# SCH_WROBD_2022_2022-09-23.net
KiCad netlist of a schematic drawn in EasyEDA
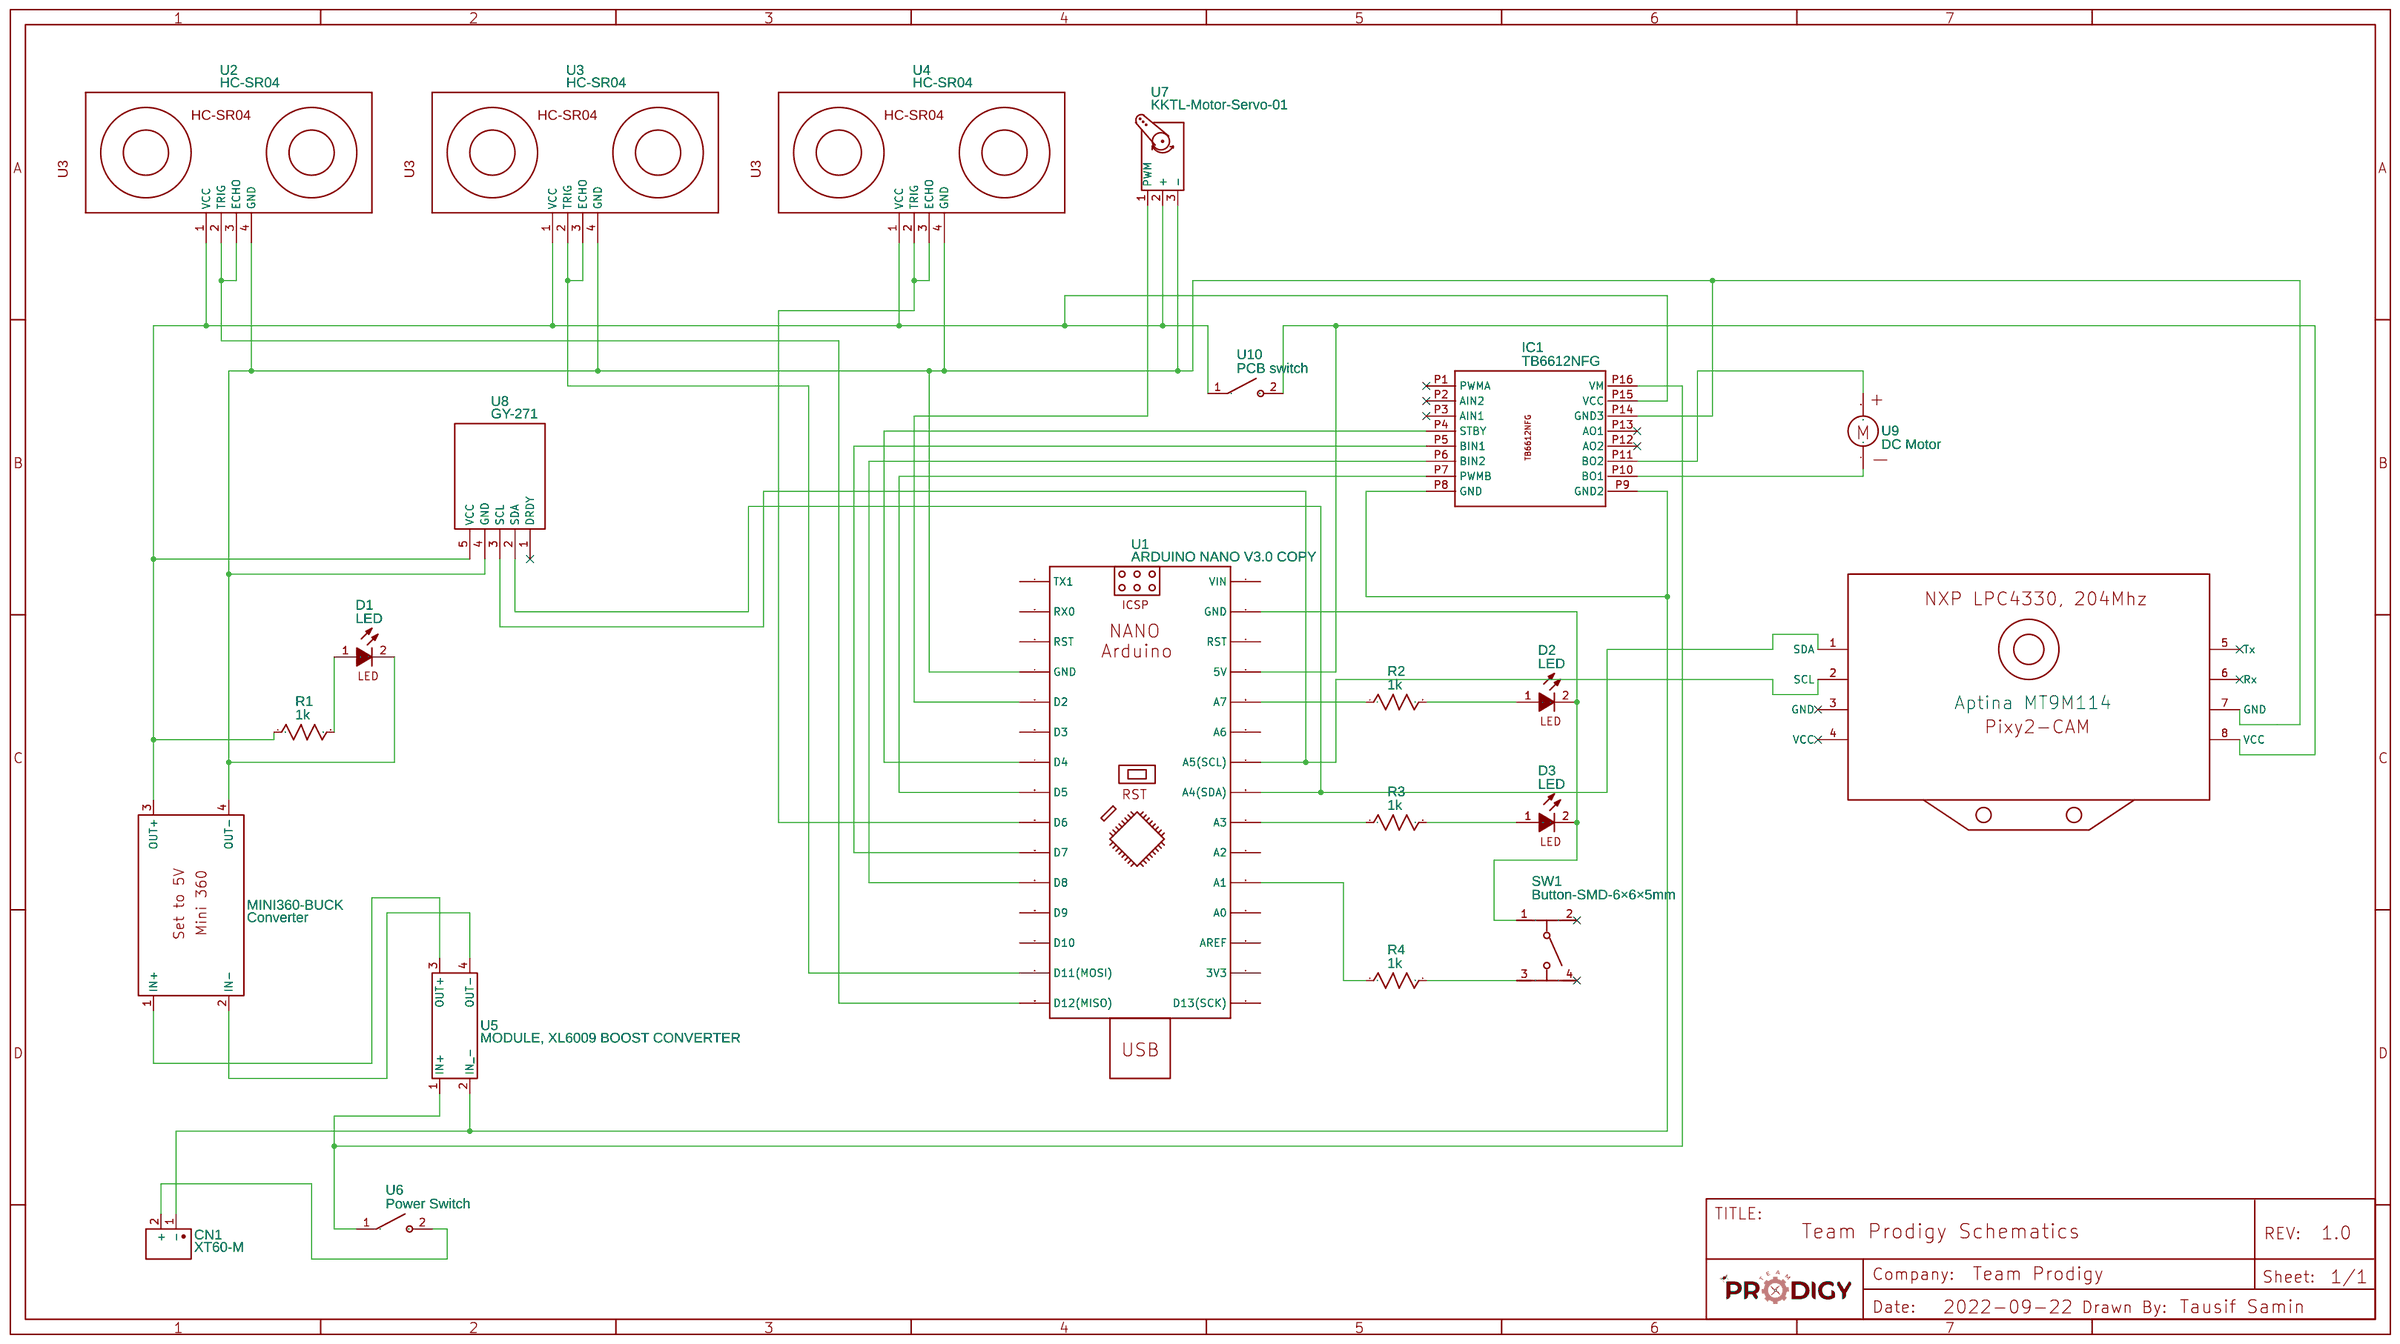
[diagram p0: schematic sheet]

(export (version "E")
  (design (tool "Eeschema 10.0.6"))
  (components
    (comp (ref "CN1")
      (value "XT60-M")
      (fields
        (field (name "BOM_Manufacturer Part") "XT60UPB-M")
        (field (name "BOM_Supplier Part") "C2918078")
      )
      (libsource (lib "") (part "XT60-M"))
    )
    (comp (ref "D1")
      (value "LED")
      (fields (field (name "BOM_Manufacturer Part") "5600") (field (name "BOM_Supplier Part") "L20325-ND"))
      (libsource (lib "") (part "LED"))
    )
    (comp (ref "D2")
      (value "LED")
      (fields (field (name "BOM_Manufacturer Part") "5600") (field (name "BOM_Supplier Part") "L20325-ND"))
      (libsource (lib "") (part "LED"))
    )
    (comp (ref "D3")
      (value "LED")
      (fields (field (name "BOM_Manufacturer Part") "5600") (field (name "BOM_Supplier Part") "L20325-ND"))
      (libsource (lib "") (part "LED"))
    )
    (comp (ref "IC1") (value "TB6612NFG") (libsource (lib "") (part "TB6612NFG")))
    (comp (ref "MINI360-BUCK")
      (value "Converter")
      (fields
        (field (name "BOM_Manufacturer Part") "DCMOD-H")
        (field (name "BOM_Supplier Part") "B078C7ZS74")
      )
      (libsource (lib "") (part "Converter"))
    )
    (comp (ref "R1") (value "1k") (libsource (lib "") (part "R_0603_US")))
    (comp (ref "R2") (value "1k") (libsource (lib "") (part "R_0603_US")))
    (comp (ref "R3") (value "1k") (libsource (lib "") (part "R_0603_US")))
    (comp (ref "R4") (value "1k") (libsource (lib "") (part "R_0603_US")))
    (comp (ref "SW1")
      (value "Button-SMD-6×6×5mm")
      (fields
        (field (name "BOM_Manufacturer Part") "6×6×5mm RHOS")
        (field (name "BOM_Supplier Part") "C21456")
      )
      (libsource (lib "") (part "Button-SMD-6×6×5mm"))
    )
    (comp (ref "U1")
      (value "ARDUINO NANO V3.0 COPY")
      (fields (field (name "BOM_Supplier Part") "XC4414"))
      (libsource (lib "") (part "ARDUINO NANO V3.0 COPY"))
    )
    (comp (ref "U2")
      (value "HC-SR04")
      (fields (field (name "BOM_Manufacturer Part") "ServoMotor"))
      (libsource (lib "") (part "HC-SR04"))
    )
    (comp (ref "U3")
      (value "HC-SR04")
      (fields (field (name "BOM_Manufacturer Part") "ServoMotor"))
      (libsource (lib "") (part "HC-SR04"))
    )
    (comp (ref "U4")
      (value "HC-SR04")
      (fields (field (name "BOM_Manufacturer Part") "ServoMotor"))
      (libsource (lib "") (part "HC-SR04"))
    )
    (comp (ref "U5")
      (value "MODULE, XL6009 BOOST CONVERTER")
      (fields (field (name "BOM_Manufacturer Part") "xl6009模块") (field (name "BOM_Supplier Part") "C2908146"))
      (libsource (lib "") (part "MODULE, XL6009 BOOST CONVERTER"))
    )
    (comp (ref "U6")
      (value "Power Switch")
      (fields (field (name "BOM_Supplier Part") "C118141"))
      (libsource (lib "") (part "PCB switch"))
    )
    (comp (ref "U7") (value "KKTL-Motor-Servo-01") (libsource (lib "") (part "KKTL-Motor-Servo-01")))
    (comp (ref "U8") (value "GY-271") (libsource (lib "") (part "GY-271")))
    (comp (ref "U9") (value "DC Motor") (libsource (lib "") (part "DC Motor")))
    (comp (ref "U10")
      (value "PCB switch")
      (fields (field (name "BOM_Supplier Part") "C118141"))
      (libsource (lib "") (part "PCB switch"))
    )
    (comp (ref "U11")
      (value "Huskylens DFRobot with Kendryte210")
      (libsource (lib "") (part "Huskylens DFRobot with Kendryte210"))
    )
  )
  (nets
    (net (code "1") (name "Net-(CN1-+)") (class "Default")
      (node (ref "CN1") (pin "2") (pinfunction "+_2") (pintype "unspecified"))
      (node (ref "U6") (pin "2") (pinfunction "2_2") (pintype "unspecified"))
    )
    (net (code "2") (name "Net-(CN1--)") (class "Default")
      (node (ref "CN1") (pin "1") (pinfunction "-_1") (pintype "unspecified"))
      (node (ref "IC1") (pin "P8") (pinfunction "GND_P8") (pintype "bidirectional"))
      (node (ref "IC1") (pin "P9") (pinfunction "GND2_P9") (pintype "bidirectional"))
      (node (ref "U5") (pin "2") (pinfunction "IN_-_2") (pintype "unspecified"))
    )
    (net (code "3") (name "Net-(D1-A)") (class "Default")
      (node (ref "D1") (pin "1") (pinfunction "A_1") (pintype "input"))
      (node (ref "R1") (pin "2") (pinfunction "2_2") (pintype "unspecified"))
    )
    (net (code "4") (name "Net-(D1-K)") (class "Default")
      (node (ref "D1") (pin "2") (pinfunction "K_2") (pintype "input"))
      (node (ref "IC1") (pin "P14") (pinfunction "GND3_P14") (pintype "bidirectional"))
      (node (ref "MINI360-BUCK") (pin "4") (pinfunction "OUT-_4") (pintype "output"))
      (node (ref "U1") (pin "4") (pinfunction "GND_4") (pintype "unspecified"))
      (node (ref "U2") (pin "4") (pinfunction "GND_4") (pintype "passive"))
      (node (ref "U3") (pin "4") (pinfunction "GND_4") (pintype "passive"))
      (node (ref "U4") (pin "4") (pinfunction "GND_4") (pintype "passive"))
      (node (ref "U7") (pin "3") (pinfunction "-_3") (pintype "unspecified"))
      (node (ref "U8") (pin "4") (pinfunction "GND_4") (pintype "unspecified"))
    )
    (net (code "5") (name "Net-(D2-A)") (class "Default")
      (node (ref "D2") (pin "1") (pinfunction "A_1") (pintype "input"))
      (node (ref "R2") (pin "2") (pinfunction "2_2") (pintype "unspecified"))
    )
    (net (code "6") (name "Net-(D2-K)") (class "Default")
      (node (ref "D2") (pin "2") (pinfunction "K_2") (pintype "input"))
      (node (ref "D3") (pin "2") (pinfunction "K_2") (pintype "input"))
      (node (ref "SW1") (pin "1") (pinfunction "1_1") (pintype "unspecified"))
      (node (ref "U1") (pin "29") (pinfunction "GND_29") (pintype "unspecified"))
    )
    (net (code "7") (name "Net-(D3-A)") (class "Default")
      (node (ref "D3") (pin "1") (pinfunction "A_1") (pintype "input"))
      (node (ref "R3") (pin "2") (pinfunction "2_2") (pintype "unspecified"))
    )
    (net (code "8") (name "Net-(IC1-BIN1)") (class "Default")
      (node (ref "IC1") (pin "P5") (pinfunction "BIN1_P5") (pintype "bidirectional"))
      (node (ref "U1") (pin "10") (pinfunction "D7_10") (pintype "unspecified"))
    )
    (net (code "9") (name "Net-(IC1-BIN2)") (class "Default")
      (node (ref "IC1") (pin "P6") (pinfunction "BIN2_P6") (pintype "bidirectional"))
      (node (ref "U1") (pin "11") (pinfunction "D8_11") (pintype "unspecified"))
    )
    (net (code "10") (name "Net-(IC1-BO1)") (class "Default")
      (node (ref "IC1") (pin "P10") (pinfunction "BO1_P10") (pintype "bidirectional"))
      (node (ref "U9") (pin "1") (pinfunction "1_1") (pintype "unspecified"))
    )
    (net (code "11") (name "Net-(IC1-BO2)") (class "Default")
      (node (ref "IC1") (pin "P11") (pinfunction "BO2_P11") (pintype "bidirectional"))
      (node (ref "U9") (pin "2") (pinfunction "2_2") (pintype "unspecified"))
    )
    (net (code "12") (name "Net-(IC1-PWMB)") (class "Default")
      (node (ref "IC1") (pin "P7") (pinfunction "PWMB_P7") (pintype "bidirectional"))
      (node (ref "U1") (pin "8") (pinfunction "D5_8") (pintype "unspecified"))
    )
    (net (code "13") (name "Net-(IC1-STBY)") (class "Default")
      (node (ref "IC1") (pin "P4") (pinfunction "STBY_P4") (pintype "bidirectional"))
      (node (ref "U1") (pin "7") (pinfunction "D4_7") (pintype "unspecified"))
    )
    (net (code "14") (name "Net-(IC1-VCC)") (class "Default")
      (node (ref "IC1") (pin "P15") (pinfunction "VCC_P15") (pintype "bidirectional"))
      (node (ref "MINI360-BUCK") (pin "3") (pinfunction "OUT+_3") (pintype "output"))
      (node (ref "R1") (pin "1") (pinfunction "1_1") (pintype "unspecified"))
      (node (ref "U10") (pin "1") (pinfunction "1_1") (pintype "unspecified"))
      (node (ref "U2") (pin "1") (pinfunction "VCC_1") (pintype "passive"))
      (node (ref "U3") (pin "1") (pinfunction "VCC_1") (pintype "passive"))
      (node (ref "U4") (pin "1") (pinfunction "VCC_1") (pintype "passive"))
      (node (ref "U7") (pin "2") (pinfunction "+_2") (pintype "unspecified"))
      (node (ref "U8") (pin "5") (pinfunction "VCC_5") (pintype "unspecified"))
    )
    (net (code "15") (name "Net-(IC1-VM)") (class "Default")
      (node (ref "IC1") (pin "P16") (pinfunction "VM_P16") (pintype "bidirectional"))
      (node (ref "U5") (pin "1") (pinfunction "IN+_1") (pintype "unspecified"))
      (node (ref "U6") (pin "1") (pinfunction "1_1") (pintype "unspecified"))
    )
    (net (code "16") (name "Net-(MINI360-BUCK-IN+)") (class "Default")
      (node (ref "MINI360-BUCK") (pin "1") (pinfunction "IN+_1") (pintype "input"))
      (node (ref "U5") (pin "3") (pinfunction "OUT+_3") (pintype "unspecified"))
    )
    (net (code "17") (name "Net-(MINI360-BUCK-IN-)") (class "Default")
      (node (ref "MINI360-BUCK") (pin "2") (pinfunction "IN-_2") (pintype "input"))
      (node (ref "U5") (pin "4") (pinfunction "OUT-_4") (pintype "unspecified"))
    )
    (net (code "18") (name "Net-(R4-Pad2)") (class "Default")
      (node (ref "R4") (pin "2") (pinfunction "2_2") (pintype "unspecified"))
      (node (ref "SW1") (pin "3") (pinfunction "3_3") (pintype "unspecified"))
    )
    (net (code "19") (name "Net-(U1-5V)") (class "Default")
      (node (ref "U1") (pin "27") (pinfunction "5V_27") (pintype "unspecified"))
      (node (ref "U10") (pin "2") (pinfunction "2_2") (pintype "unspecified"))
    )
    (net (code "20") (name "Net-(U1-A1)") (class "Default")
      (node (ref "R4") (pin "1") (pinfunction "1_1") (pintype "unspecified"))
      (node (ref "U1") (pin "20") (pinfunction "A1_20") (pintype "unspecified"))
    )
    (net (code "21") (name "Net-(U1-A3)") (class "Default")
      (node (ref "R3") (pin "1") (pinfunction "1_1") (pintype "unspecified"))
      (node (ref "U1") (pin "22") (pinfunction "A3_22") (pintype "unspecified"))
    )
    (net (code "22") (name "Net-(U1-A4(SDA))") (class "Default")
      (node (ref "U1") (pin "23") (pinfunction "A4(SDA)_23") (pintype "unspecified"))
      (node (ref "U8") (pin "2") (pinfunction "SDA_2") (pintype "unspecified"))
    )
    (net (code "23") (name "Net-(U1-A5(SCL))") (class "Default")
      (node (ref "U1") (pin "24") (pinfunction "A5(SCL)_24") (pintype "unspecified"))
      (node (ref "U8") (pin "3") (pinfunction "SCL_3") (pintype "unspecified"))
    )
    (net (code "24") (name "Net-(U1-A7)") (class "Default")
      (node (ref "R2") (pin "1") (pinfunction "1_1") (pintype "unspecified"))
      (node (ref "U1") (pin "26") (pinfunction "A7_26") (pintype "unspecified"))
    )
    (net (code "25") (name "Net-(U1-D2)") (class "Default")
      (node (ref "U1") (pin "5") (pinfunction "D2_5") (pintype "unspecified"))
      (node (ref "U7") (pin "1") (pinfunction "PWM_1") (pintype "unspecified"))
    )
    (net (code "26") (name "Net-(U1-D6)") (class "Default")
      (node (ref "U1") (pin "9") (pinfunction "D6_9") (pintype "unspecified"))
      (node (ref "U4") (pin "2") (pinfunction "TRIG_2") (pintype "input"))
      (node (ref "U4") (pin "3") (pinfunction "ECHO_3") (pintype "output"))
    )
    (net (code "27") (name "Net-(U1-D11(MOSI))") (class "Default")
      (node (ref "U1") (pin "14") (pinfunction "D11(MOSI)_14") (pintype "unspecified"))
      (node (ref "U3") (pin "2") (pinfunction "TRIG_2") (pintype "input"))
      (node (ref "U3") (pin "3") (pinfunction "ECHO_3") (pintype "output"))
    )
    (net (code "28") (name "Net-(U1-D12(MISO))") (class "Default")
      (node (ref "U1") (pin "15") (pinfunction "D12(MISO)_15") (pintype "unspecified"))
      (node (ref "U2") (pin "2") (pinfunction "TRIG_2") (pintype "input"))
      (node (ref "U2") (pin "3") (pinfunction "ECHO_3") (pintype "output"))
    )
    (net (code "29") (name "unconnected-(IC1-AIN1-PadP3)") (class "Default")
      (node (ref "IC1") (pin "P3") (pinfunction "AIN1_P3") (pintype "bidirectional+no_connect"))
    )
    (net (code "30") (name "unconnected-(IC1-AIN2-PadP2)") (class "Default")
      (node (ref "IC1") (pin "P2") (pinfunction "AIN2_P2") (pintype "bidirectional+no_connect"))
    )
    (net (code "31") (name "unconnected-(IC1-AO1-PadP13)") (class "Default")
      (node (ref "IC1") (pin "P13") (pinfunction "AO1_P13") (pintype "bidirectional+no_connect"))
    )
    (net (code "32") (name "unconnected-(IC1-AO2-PadP12)") (class "Default")
      (node (ref "IC1") (pin "P12") (pinfunction "AO2_P12") (pintype "bidirectional+no_connect"))
    )
    (net (code "33") (name "unconnected-(IC1-PWMA-PadP1)") (class "Default")
      (node (ref "IC1") (pin "P1") (pinfunction "PWMA_P1") (pintype "bidirectional+no_connect"))
    )
    (net (code "34") (name "unconnected-(SW1-Pad2)") (class "Default")
      (node (ref "SW1") (pin "2") (pinfunction "2_2") (pintype "unspecified+no_connect"))
    )
    (net (code "35") (name "unconnected-(SW1-Pad4)") (class "Default")
      (node (ref "SW1") (pin "4") (pinfunction "4_4") (pintype "unspecified+no_connect"))
    )
    (net (code "36") (name "unconnected-(U1-3V3-Pad17)") (class "Default")
      (node (ref "U1") (pin "17") (pinfunction "3V3_17") (pintype "unspecified"))
    )
    (net (code "37") (name "unconnected-(U1-A0-Pad19)") (class "Default")
      (node (ref "U1") (pin "19") (pinfunction "A0_19") (pintype "unspecified"))
    )
    (net (code "38") (name "unconnected-(U1-A2-Pad21)") (class "Default")
      (node (ref "U1") (pin "21") (pinfunction "A2_21") (pintype "unspecified"))
    )
    (net (code "39") (name "unconnected-(U1-A6-Pad25)") (class "Default")
      (node (ref "U1") (pin "25") (pinfunction "A6_25") (pintype "unspecified"))
    )
    (net (code "40") (name "unconnected-(U1-AREF-Pad18)") (class "Default")
      (node (ref "U1") (pin "18") (pinfunction "AREF_18") (pintype "unspecified"))
    )
    (net (code "41") (name "unconnected-(U1-D3-Pad6)") (class "Default")
      (node (ref "U1") (pin "6") (pinfunction "D3_6") (pintype "unspecified"))
    )
    (net (code "42") (name "unconnected-(U1-D9-Pad12)") (class "Default")
      (node (ref "U1") (pin "12") (pinfunction "D9_12") (pintype "unspecified"))
    )
    (net (code "43") (name "unconnected-(U1-D10-Pad13)") (class "Default")
      (node (ref "U1") (pin "13") (pinfunction "D10_13") (pintype "unspecified"))
    )
    (net (code "44") (name "unconnected-(U1-D13(SCK)-Pad16)") (class "Default")
      (node (ref "U1") (pin "16") (pinfunction "D13(SCK)_16") (pintype "unspecified"))
    )
    (net (code "45") (name "unconnected-(U1-RST-Pad3)") (class "Default")
      (node (ref "U1") (pin "3") (pinfunction "RST_3") (pintype "unspecified"))
    )
    (net (code "46") (name "unconnected-(U1-RST-Pad28)") (class "Default")
      (node (ref "U1") (pin "28") (pinfunction "RST_28") (pintype "unspecified"))
    )
    (net (code "47") (name "unconnected-(U1-RX0-Pad2)") (class "Default")
      (node (ref "U1") (pin "2") (pinfunction "RX0_2") (pintype "unspecified"))
    )
    (net (code "48") (name "unconnected-(U1-TX1-Pad1)") (class "Default")
      (node (ref "U1") (pin "1") (pinfunction "TX1_1") (pintype "unspecified"))
    )
    (net (code "49") (name "unconnected-(U1-VIN-Pad30)") (class "Default")
      (node (ref "U1") (pin "30") (pinfunction "VIN_30") (pintype "unspecified"))
    )
    (net (code "50") (name "unconnected-(U8-DRDY-Pad1)") (class "Default")
      (node (ref "U8") (pin "1") (pinfunction "DRDY_1") (pintype "unspecified+no_connect"))
    )
    (net (code "51") (name "unconnected-(U11-GND-Pad3)") (class "Default")
      (node (ref "U11") (pin "3") (pinfunction "GND_3") (pintype "unspecified"))
    )
    (net (code "52") (name "unconnected-(U11-GND-Pad7)") (class "Default")
      (node (ref "U11") (pin "7") (pinfunction "GND_7") (pintype "unspecified"))
    )
    (net (code "53") (name "unconnected-(U11-Rx-Pad6)") (class "Default")
      (node (ref "U11") (pin "6") (pinfunction "Rx_6") (pintype "unspecified"))
    )
    (net (code "54") (name "unconnected-(U11-SCL-Pad2)") (class "Default")
      (node (ref "U11") (pin "2") (pinfunction "SCL_2") (pintype "unspecified"))
    )
    (net (code "55") (name "unconnected-(U11-SDA-Pad1)") (class "Default")
      (node (ref "U11") (pin "1") (pinfunction "SDA_1") (pintype "unspecified"))
    )
    (net (code "56") (name "unconnected-(U11-Tx-Pad5)") (class "Default")
      (node (ref "U11") (pin "5") (pinfunction "Tx_5") (pintype "unspecified"))
    )
    (net (code "57") (name "unconnected-(U11-VCC-Pad4)") (class "Default")
      (node (ref "U11") (pin "4") (pinfunction "VCC_4") (pintype "unspecified"))
    )
    (net (code "58") (name "unconnected-(U11-VCC-Pad8)") (class "Default")
      (node (ref "U11") (pin "8") (pinfunction "VCC_8") (pintype "unspecified"))
    )
  )
)
